# Max756Breakout.net
KiCad netlist of a schematic drawn in EAGLE
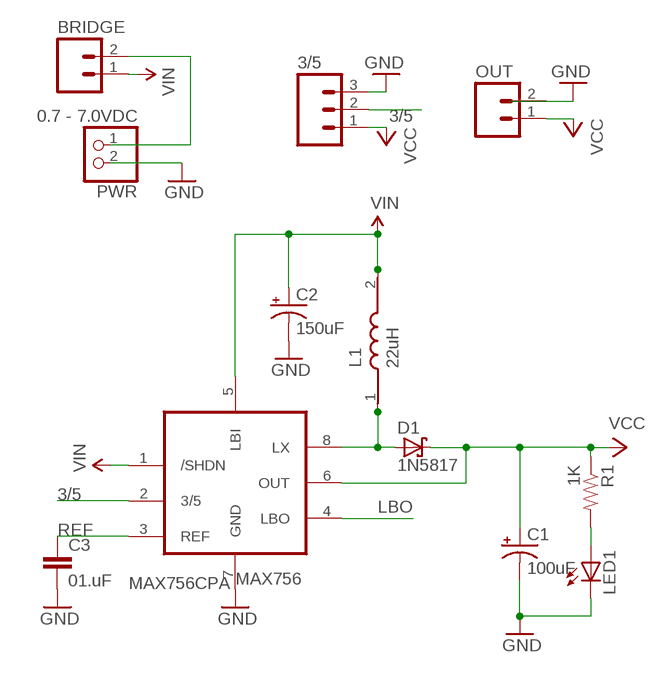
[diagram p0: schematic, sheet 1]

(export (version "E")
  (design (tool "Eeschema 10.0.6"))
  (components
    (comp (ref "3/5")
      (value "M03LOCK")
      (footprint "eagle-import:1X03_LOCK")
      (libsource (lib "eagle-import") (part "M03LOCK"))
    )
    (comp (ref "BRIDGE")
      (value "M02LOCK")
      (footprint "eagle-import:1X02_LOCK")
      (libsource (lib "eagle-import") (part "M02LOCK"))
    )
    (comp (ref "C1")
      (value "100uF")
      (footprint "eagle-import:CPOL-RADIAL-10UF-25V")
      (libsource (lib "eagle-import") (part "CAP_POLPTH2"))
    )
    (comp (ref "C2")
      (value "150uF")
      (footprint "eagle-import:CPOL-RADIAL-10UF-25V")
      (libsource (lib "eagle-import") (part "CAP_POLPTH2"))
    )
    (comp (ref "C3")
      (value "01.uF")
      (footprint "eagle-import:CAP-PTH-SMALL2")
      (libsource (lib "eagle-import") (part "CAPPTH2"))
    )
    (comp (ref "D1")
      (value "1N5817")
      (footprint "eagle-import:F126Z12")
      (libsource (lib "eagle-import") (part "SCHOTTKY-DIODEF126Z12"))
    )
    (comp (ref "L1")
      (value "22uH")
      (footprint "eagle-import:82114R")
      (libsource (lib "eagle-import") (part "82114R"))
    )
    (comp (ref "LED1")
      (value "LED3MM")
      (footprint "eagle-import:LED3MM")
      (libsource (lib "eagle-import") (part "LED3MM"))
    )
    (comp (ref "MAX756")
      (value "MAX756CPA")
      (footprint "eagle-import:DIL08")
      (libsource (lib "eagle-import") (part "MAX756CPA"))
    )
    (comp (ref "OUT")
      (value "M02LOCK")
      (footprint "eagle-import:1X02_LOCK")
      (libsource (lib "eagle-import") (part "M02LOCK"))
    )
    (comp (ref "PWR")
      (value "0.7 - 7.0VDC")
      (footprint "eagle-import:JST-PH-2-THM-RA")
      (libsource (lib "eagle-import") (part "JST_2PIN-THM-RA"))
    )
    (comp (ref "R1")
      (value "1K")
      (footprint "eagle-import:AXIAL-0.2")
      (libsource (lib "eagle-import") (part "RESISTORAXIAL-0.2"))
    )
  )
  (nets
    (net (code "1") (name "/3{slash}5") (class "Default")
      (node (ref "3/5") (pin "2") (pinfunction "2_2") (pintype "passive"))
      (node (ref "MAX756") (pin "2") (pinfunction "3/5_2") (pintype "bidirectional"))
    )
    (net (code "2") (name "/LBO") (class "Default")
      (node (ref "MAX756") (pin "4") (pinfunction "LBO_4") (pintype "input"))
    )
    (net (code "3") (name "/REF") (class "Default")
      (node (ref "C3") (pin "1") (pinfunction "1_1") (pintype "passive"))
      (node (ref "MAX756") (pin "3") (pinfunction "REF_3") (pintype "passive"))
    )
    (net (code "4") (name "GND") (class "Default")
      (node (ref "3/5") (pin "3") (pinfunction "3_3") (pintype "passive"))
      (node (ref "C1") (pin "2") (pinfunction "-_2") (pintype "passive"))
      (node (ref "C2") (pin "2") (pinfunction "-_2") (pintype "passive"))
      (node (ref "C3") (pin "2") (pinfunction "2_2") (pintype "passive"))
      (node (ref "LED1") (pin "K") (pinfunction "C_K") (pintype "passive"))
      (node (ref "MAX756") (pin "7") (pinfunction "GND_7") (pintype "power_in"))
      (node (ref "OUT") (pin "2") (pinfunction "2_2") (pintype "passive"))
      (node (ref "PWR") (pin "2") (pinfunction "1_2") (pintype "passive"))
    )
    (net (code "5") (name "Net-(MAX756-LX)") (class "Default")
      (node (ref "D1") (pin "A") (pinfunction "A_A") (pintype "passive"))
      (node (ref "L1") (pin "1") (pinfunction "1_1") (pintype "passive"))
      (node (ref "MAX756") (pin "8") (pinfunction "LX_8") (pintype "output"))
    )
    (net (code "6") (name "Net-(PWR-2)") (class "Default")
      (node (ref "BRIDGE") (pin "2") (pinfunction "2_2") (pintype "passive"))
      (node (ref "PWR") (pin "1") (pinfunction "2_1") (pintype "passive"))
    )
    (net (code "7") (name "Net-(R1-2)") (class "Default")
      (node (ref "LED1") (pin "A") (pinfunction "A_A") (pintype "passive"))
      (node (ref "R1") (pin "P$2") (pinfunction "2_P$2") (pintype "passive"))
    )
    (net (code "8") (name "VCC") (class "Default")
      (node (ref "3/5") (pin "1") (pinfunction "1_1") (pintype "passive"))
      (node (ref "C1") (pin "1") (pinfunction "+_1") (pintype "passive"))
      (node (ref "D1") (pin "C") (pinfunction "C_C") (pintype "passive"))
      (node (ref "MAX756") (pin "6") (pinfunction "OUT_6") (pintype "output"))
      (node (ref "OUT") (pin "1") (pinfunction "1_1") (pintype "passive"))
      (node (ref "R1") (pin "P$1") (pinfunction "1_P$1") (pintype "passive"))
    )
    (net (code "9") (name "VIN") (class "Default")
      (node (ref "BRIDGE") (pin "1") (pinfunction "1_1") (pintype "passive"))
      (node (ref "C2") (pin "1") (pinfunction "+_1") (pintype "passive"))
      (node (ref "L1") (pin "2") (pinfunction "2_2") (pintype "passive"))
      (node (ref "MAX756") (pin "1") (pinfunction "/SHDN_1") (pintype "input"))
      (node (ref "MAX756") (pin "5") (pinfunction "LBI_5") (pintype "input"))
    )
  )
)
